# Main.net
KiCad netlist of a schematic drawn in Altium Designer
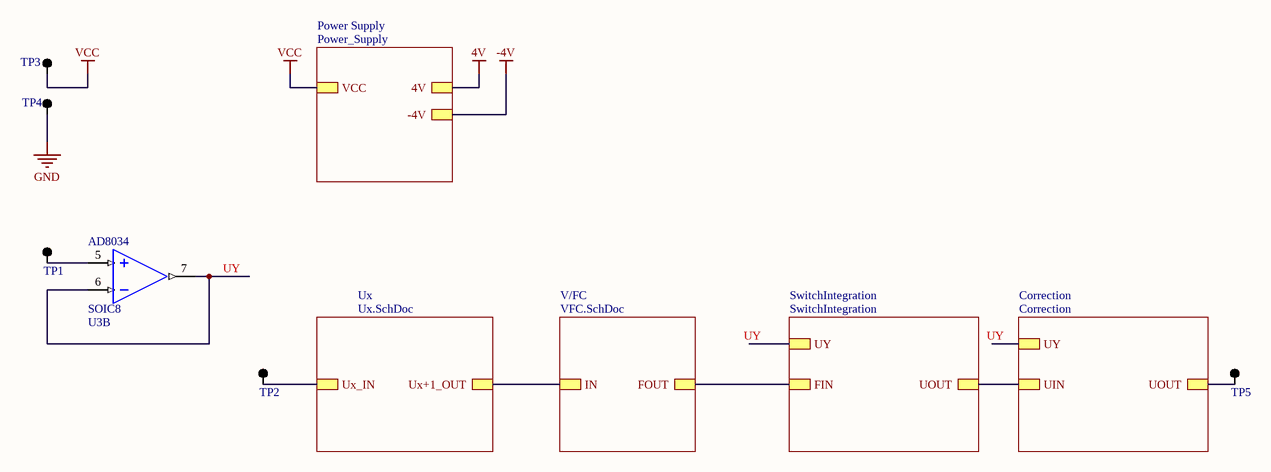
[diagram p0: Main.SchDoc]

(export (version "E")
  (design (tool "Eeschema 10.0.6"))
  (components
    (comp (ref "TP1")
      (value "Single pin")
      (footprint "TP_1PIN")
      (description "Testpoint")
      (fields (field (name "PART NUMBER") "TP_1PIN"))
      (libsource (lib "Library") (part "TP_TESTPOINT"))
    )
    (comp (ref "TP2")
      (value "Single pin")
      (footprint "TP_1PIN")
      (description "Testpoint")
      (fields (field (name "PART NUMBER") "TP_1PIN"))
      (libsource (lib "Library") (part "TP_TESTPOINT"))
    )
    (comp (ref "TP3")
      (value "Single pin")
      (footprint "TP_1PIN")
      (description "Testpoint")
      (fields (field (name "PART NUMBER") "TP_1PIN"))
      (libsource (lib "Library") (part "TP_TESTPOINT"))
    )
    (comp (ref "TP4")
      (value "Single pin")
      (footprint "TP_1PIN")
      (description "Testpoint")
      (fields (field (name "PART NUMBER") "TP_1PIN"))
      (libsource (lib "Library") (part "TP_TESTPOINT"))
    )
    (comp (ref "TP5")
      (value "Single pin")
      (footprint "TP_1PIN")
      (description "Testpoint")
      (fields (field (name "PART NUMBER") "TP_1PIN"))
      (libsource (lib "Library") (part "TP_TESTPOINT"))
    )
    (comp (ref "U3")
      (value "AD8034")
      (footprint "SO8")
      (fields (field (name "SCH_FOOTPRINT") "SOIC8") (field (name "Comment") "A2_AD8034"))
      (libsource (lib "SIUE_Symbol") (part "A2_AD8034"))
    )
  )
  (nets
    (net (code "5") (name "/UOUT") (class "Default")
      (node (ref "TP5") (pin "1") (pinfunction "TP_1") (pintype "passive"))
    )
    (net (code "6") (name "/UY") (class "Default")
      (node (ref "U3") (pin "6") (pinfunction "IN-2_6") (pintype "input"))
      (node (ref "U3") (pin "7") (pinfunction "OUT2_7") (pintype "output"))
    )
    (net (code "7") (name "/Ux_IN") (class "Default")
      (node (ref "TP2") (pin "1") (pinfunction "TP_1") (pintype "passive"))
    )
    (net (code "9") (name "GND") (class "Default")
      (node (ref "TP4") (pin "1") (pinfunction "TP_1") (pintype "passive"))
    )
    (net (code "10") (name "Net-(TP1-TP)") (class "Default")
      (node (ref "TP1") (pin "1") (pinfunction "TP_1") (pintype "passive"))
      (node (ref "U3") (pin "5") (pinfunction "IN+2_5") (pintype "input"))
    )
    (net (code "11") (name "VCC") (class "Default")
      (node (ref "TP3") (pin "1") (pinfunction "TP_1") (pintype "passive"))
    )
  )
)
